# Power_Input.net
KiCad netlist of a schematic drawn in Altium Designer
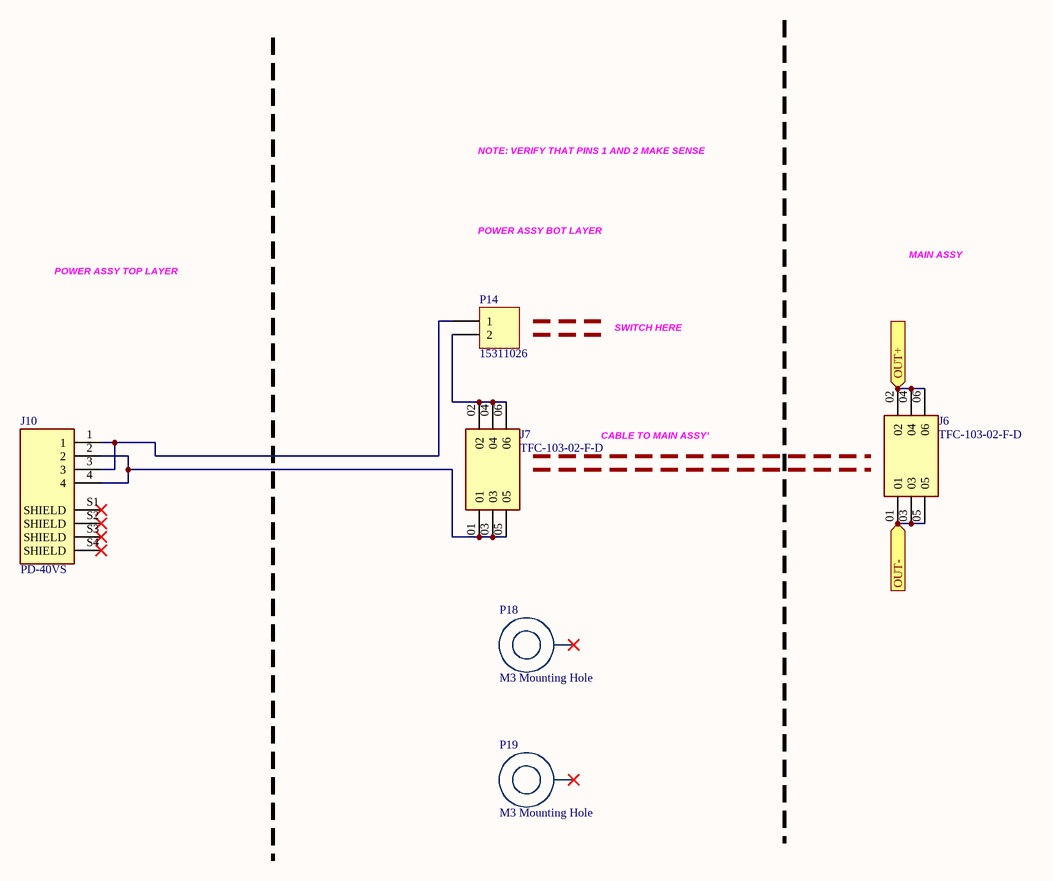
[diagram p0: Power_Input.SchDoc]

(export (version "E")
  (design (tool "Eeschema 10.0.6"))
  (components
    (comp (ref "J6")
      (value "TFC-103-02-F-D")
      (footprint "Arturo_Approved:SAMTEC_TFC-103-02-F-D")
      (fields (field (name "MF") "Samtec"))
      (libsource (lib "Arturo_Approved") (part "TFC-103-02-F-D"))
    )
    (comp (ref "J7")
      (value "TFC-103-02-F-D")
      (footprint "Arturo_Approved:SAMTEC_TFC-103-02-F-D")
      (fields (field (name "MF") "Samtec"))
      (libsource (lib "Arturo_Approved") (part "TFC-103-02-F-D"))
    )
    (comp (ref "J10")
      (value "PD-40VS")
      (footprint "Arturo_Approved:CUI_PD-40VS")
      (description "4 Position , 7.5 A, Vertical, Through Hole, Shielded, Power DIN Connector")
      (fields (field (name "MF") "{'manufacturer': u'CUI'}"))
      (libsource (lib "Arturo_Approved") (part "PD-40VS"))
    )
    (comp (ref "P14")
      (value "15311026")
      (footprint "HDR1X2")
      (description "Header, 2-Pin")
      (fields (field (name "PUBLISHER") "Altium Limited"))
      (libsource (lib "Miscellaneous Connectors") (part "Header 2"))
    )
    (comp (ref "P18")
      (value "M3 Mounting Hole")
      (footprint "MH-M3")
      (libsource (lib "Arturo_Approved") (part "MH-M3"))
    )
    (comp (ref "P19")
      (value "M3 Mounting Hole")
      (footprint "MH-M3")
      (libsource (lib "Arturo_Approved") (part "MH-M3"))
    )
  )
  (nets
    (net (code "1") (name "/OUT+") (class "Default")
      (node (ref "J6") (pin "02") (pinfunction "02_02") (pintype "passive"))
      (node (ref "J6") (pin "04") (pinfunction "04_04") (pintype "passive"))
      (node (ref "J6") (pin "06") (pinfunction "06_06") (pintype "passive"))
    )
    (net (code "2") (name "/OUT-") (class "Default")
      (node (ref "J6") (pin "01") (pinfunction "01_01") (pintype "passive"))
      (node (ref "J6") (pin "03") (pinfunction "03_03") (pintype "passive"))
      (node (ref "J6") (pin "05") (pinfunction "05_05") (pintype "passive"))
    )
    (net (code "3") (name "Net-(J7-Pad02)") (class "Default")
      (node (ref "J7") (pin "02") (pinfunction "02_02") (pintype "passive"))
      (node (ref "J7") (pin "04") (pinfunction "04_04") (pintype "passive"))
      (node (ref "J7") (pin "06") (pinfunction "06_06") (pintype "passive"))
      (node (ref "P14") (pin "2") (pinfunction "2_2") (pintype "passive"))
    )
    (net (code "4") (name "Net-(J10-Pad1)") (class "Default")
      (node (ref "J10") (pin "1") (pinfunction "1_1") (pintype "passive"))
      (node (ref "J10") (pin "3") (pinfunction "3_3") (pintype "passive"))
      (node (ref "P14") (pin "1") (pinfunction "1_1") (pintype "passive"))
    )
    (net (code "5") (name "Net-(J10-Pad2)") (class "Default")
      (node (ref "J10") (pin "2") (pinfunction "2_2") (pintype "passive"))
      (node (ref "J10") (pin "4") (pinfunction "4_4") (pintype "passive"))
      (node (ref "J7") (pin "01") (pinfunction "01_01") (pintype "passive"))
      (node (ref "J7") (pin "03") (pinfunction "03_03") (pintype "passive"))
      (node (ref "J7") (pin "05") (pinfunction "05_05") (pintype "passive"))
    )
    (net (code "6") (name "unconnected-(J10-SHIELD-PadS1)") (class "Default")
      (node (ref "J10") (pin "S1") (pinfunction "SHIELD_S1") (pintype "passive+no_connect"))
    )
    (net (code "7") (name "unconnected-(J10-SHIELD-PadS2)") (class "Default")
      (node (ref "J10") (pin "S2") (pinfunction "SHIELD_S2") (pintype "passive+no_connect"))
    )
    (net (code "8") (name "unconnected-(J10-SHIELD-PadS3)") (class "Default")
      (node (ref "J10") (pin "S3") (pinfunction "SHIELD_S3") (pintype "passive+no_connect"))
    )
    (net (code "9") (name "unconnected-(J10-SHIELD-PadS4)") (class "Default")
      (node (ref "J10") (pin "S4") (pinfunction "SHIELD_S4") (pintype "passive+no_connect"))
    )
    (net (code "10") (name "unconnected-(P18-Pad1)") (class "Default")
      (node (ref "P18") (pin "1") (pinfunction "1_1") (pintype "passive+no_connect"))
    )
    (net (code "11") (name "unconnected-(P19-Pad1)") (class "Default")
      (node (ref "P19") (pin "1") (pinfunction "1_1") (pintype "passive+no_connect"))
    )
  )
)
